# BD0007_1_5x.net
KiCad netlist of a schematic drawn in EAGLE
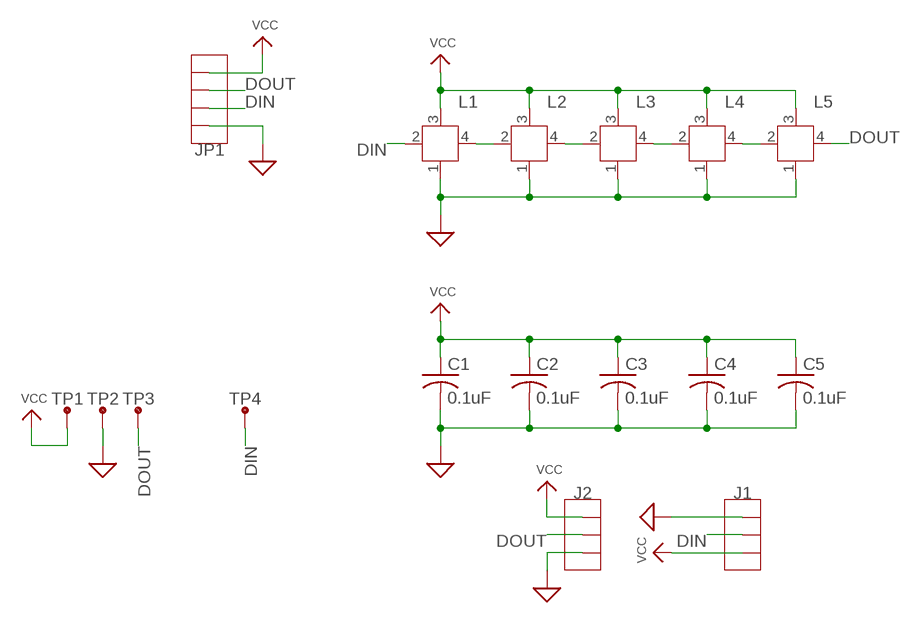
[diagram p0: schematic, sheet 1]

(export (version "E")
  (design (tool "Eeschema 10.0.6"))
  (components
    (comp (ref "C1")
      (value "0.1uF")
      (footprint "eagle-import:C0402")
      (libsource (lib "eagle-import") (part "C-USC0402"))
    )
    (comp (ref "C2")
      (value "0.1uF")
      (footprint "eagle-import:C0402")
      (libsource (lib "eagle-import") (part "C-USC0402"))
    )
    (comp (ref "C3")
      (value "0.1uF")
      (footprint "eagle-import:C0402")
      (libsource (lib "eagle-import") (part "C-USC0402"))
    )
    (comp (ref "C4")
      (value "0.1uF")
      (footprint "eagle-import:C0402")
      (libsource (lib "eagle-import") (part "C-USC0402"))
    )
    (comp (ref "C5")
      (value "0.1uF")
      (footprint "eagle-import:C0402")
      (libsource (lib "eagle-import") (part "C-USC0402"))
    )
    (comp (ref "J1")
      (value "HEADER_1X3MALE")
      (footprint "eagle-import:M3SMD")
      (libsource (lib "eagle-import") (part "HEADER_1X3MALE"))
    )
    (comp (ref "J2")
      (value "HEADER_1X3FEMALE")
      (footprint "eagle-import:F3SMD")
      (libsource (lib "eagle-import") (part "HEADER_1X3FEMALE"))
    )
    (comp (ref "JP1")
      (value "HEADER_1X4S")
      (footprint "eagle-import:1X04")
      (libsource (lib "eagle-import") (part "HEADER_1X4S"))
    )
    (comp (ref "L1")
      (value "WS2812B")
      (footprint "eagle-import:SK6812")
      (libsource (lib "eagle-import") (part "WS2812B"))
    )
    (comp (ref "L2")
      (value "WS2812B")
      (footprint "eagle-import:SK6812")
      (libsource (lib "eagle-import") (part "WS2812B"))
    )
    (comp (ref "L3")
      (value "WS2812B")
      (footprint "eagle-import:SK6812")
      (libsource (lib "eagle-import") (part "WS2812B"))
    )
    (comp (ref "L4")
      (value "WS2812B")
      (footprint "eagle-import:SK6812")
      (libsource (lib "eagle-import") (part "WS2812B"))
    )
    (comp (ref "L5")
      (value "WS2812B")
      (footprint "eagle-import:SK6812")
      (libsource (lib "eagle-import") (part "WS2812B"))
    )
    (comp (ref "TP1")
      (value "VCC")
      (footprint "eagle-import:TEST_POINT")
      (libsource (lib "eagle-import") (part "TEST_POINT"))
    )
    (comp (ref "TP2")
      (value "GND")
      (footprint "eagle-import:TEST_POINT")
      (libsource (lib "eagle-import") (part "TEST_POINT"))
    )
    (comp (ref "TP3")
      (value "DOUT")
      (footprint "eagle-import:TEST_POINT")
      (libsource (lib "eagle-import") (part "TEST_POINT"))
    )
    (comp (ref "TP4")
      (value "DIN")
      (footprint "eagle-import:TEST_POINT")
      (libsource (lib "eagle-import") (part "TEST_POINT"))
    )
  )
  (nets
    (net (code "1") (name "/DIN") (class "Default")
      (node (ref "J1") (pin "2") (pinfunction "P$2_2") (pintype "bidirectional"))
      (node (ref "JP1") (pin "2") (pinfunction "P$2_2") (pintype "bidirectional"))
      (node (ref "L1") (pin "2") (pinfunction "DIN_2") (pintype "bidirectional"))
      (node (ref "TP4") (pin "P$1") (pinfunction "P$1_P$1") (pintype "input"))
    )
    (net (code "2") (name "/DOUT") (class "Default")
      (node (ref "J2") (pin "2A") (pinfunction "P$2_2A") (pintype "bidirectional"))
      (node (ref "J2") (pin "2B") (pinfunction "P$2_2B") (pintype "bidirectional"))
      (node (ref "JP1") (pin "3") (pinfunction "P$3_3") (pintype "bidirectional"))
      (node (ref "L5") (pin "4") (pinfunction "DOUT_4") (pintype "bidirectional"))
      (node (ref "TP3") (pin "P$1") (pinfunction "P$1_P$1") (pintype "input"))
    )
    (net (code "3") (name "Net-(L1-DOUT)") (class "Default")
      (node (ref "L1") (pin "4") (pinfunction "DOUT_4") (pintype "bidirectional"))
      (node (ref "L2") (pin "2") (pinfunction "DIN_2") (pintype "bidirectional"))
    )
    (net (code "4") (name "Net-(L2-DOUT)") (class "Default")
      (node (ref "L2") (pin "4") (pinfunction "DOUT_4") (pintype "bidirectional"))
      (node (ref "L3") (pin "2") (pinfunction "DIN_2") (pintype "bidirectional"))
    )
    (net (code "5") (name "Net-(L3-DOUT)") (class "Default")
      (node (ref "L3") (pin "4") (pinfunction "DOUT_4") (pintype "bidirectional"))
      (node (ref "L4") (pin "2") (pinfunction "DIN_2") (pintype "bidirectional"))
    )
    (net (code "6") (name "Net-(L4-DOUT)") (class "Default")
      (node (ref "L4") (pin "4") (pinfunction "DOUT_4") (pintype "bidirectional"))
      (node (ref "L5") (pin "2") (pinfunction "DIN_2") (pintype "bidirectional"))
    )
    (net (code "7") (name "SUP") (class "Default")
      (node (ref "C1") (pin "2") (pinfunction "2_2") (pintype "passive"))
      (node (ref "C2") (pin "2") (pinfunction "2_2") (pintype "passive"))
      (node (ref "C3") (pin "2") (pinfunction "2_2") (pintype "passive"))
      (node (ref "C4") (pin "2") (pinfunction "2_2") (pintype "passive"))
      (node (ref "C5") (pin "2") (pinfunction "2_2") (pintype "passive"))
      (node (ref "J1") (pin "1") (pinfunction "P$1_1") (pintype "bidirectional"))
      (node (ref "J2") (pin "3A") (pinfunction "P$3_3A") (pintype "bidirectional"))
      (node (ref "J2") (pin "3B") (pinfunction "P$3_3B") (pintype "bidirectional"))
      (node (ref "JP1") (pin "1") (pinfunction "P$1_1") (pintype "bidirectional"))
      (node (ref "L1") (pin "1") (pinfunction "VSS_1") (pintype "bidirectional"))
      (node (ref "L2") (pin "1") (pinfunction "VSS_1") (pintype "bidirectional"))
      (node (ref "L3") (pin "1") (pinfunction "VSS_1") (pintype "bidirectional"))
      (node (ref "L4") (pin "1") (pinfunction "VSS_1") (pintype "bidirectional"))
      (node (ref "L5") (pin "1") (pinfunction "VSS_1") (pintype "bidirectional"))
      (node (ref "TP2") (pin "P$1") (pinfunction "P$1_P$1") (pintype "input"))
    )
    (net (code "8") (name "VCC") (class "Default")
      (node (ref "C1") (pin "1") (pinfunction "1_1") (pintype "passive"))
      (node (ref "C2") (pin "1") (pinfunction "1_1") (pintype "passive"))
      (node (ref "C3") (pin "1") (pinfunction "1_1") (pintype "passive"))
      (node (ref "C4") (pin "1") (pinfunction "1_1") (pintype "passive"))
      (node (ref "C5") (pin "1") (pinfunction "1_1") (pintype "passive"))
      (node (ref "J1") (pin "3") (pinfunction "P$3_3") (pintype "bidirectional"))
      (node (ref "J2") (pin "1A") (pinfunction "P$1_1A") (pintype "bidirectional"))
      (node (ref "J2") (pin "1B") (pinfunction "P$1_1B") (pintype "bidirectional"))
      (node (ref "JP1") (pin "4") (pinfunction "P$4_4") (pintype "bidirectional"))
      (node (ref "L1") (pin "3") (pinfunction "VDD_3") (pintype "bidirectional"))
      (node (ref "L2") (pin "3") (pinfunction "VDD_3") (pintype "bidirectional"))
      (node (ref "L3") (pin "3") (pinfunction "VDD_3") (pintype "bidirectional"))
      (node (ref "L4") (pin "3") (pinfunction "VDD_3") (pintype "bidirectional"))
      (node (ref "L5") (pin "3") (pinfunction "VDD_3") (pintype "bidirectional"))
      (node (ref "TP1") (pin "P$1") (pinfunction "P$1_P$1") (pintype "input"))
    )
  )
)
